# AD628.net
KiCad netlist of a schematic drawn in Altium Designer
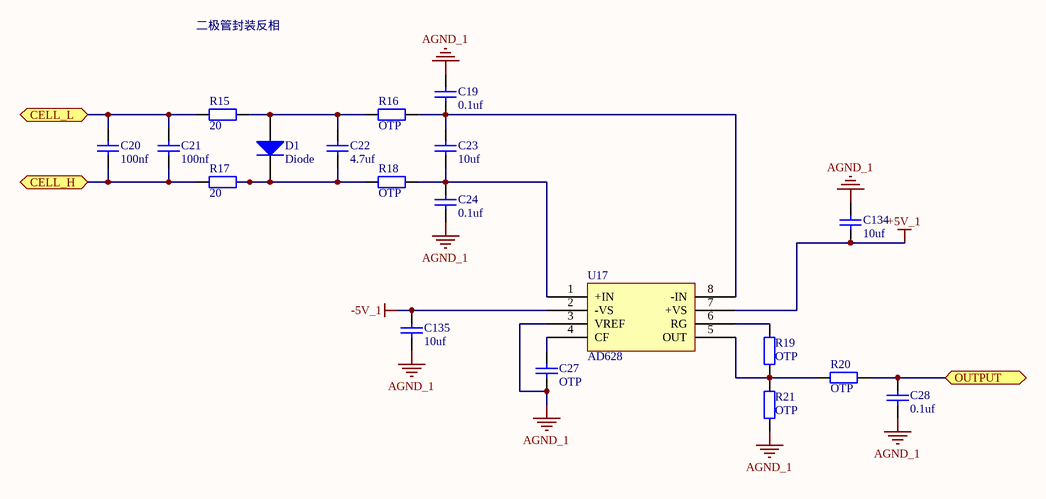
[diagram p0: AD628模块.SchDoc]

(export (version "E")
  (design (tool "Eeschema 10.0.6"))
  (components
    (comp (ref "C19")
      (value "0.1uf")
      (footprint "0805C")
      (description "Capacitor")
      (fields (field (name "Comment") "Cap") (field (name "PUBLISHER") "Altium Limited"))
      (libsource (lib "Miscellaneous Devices") (part "Cap"))
    )
    (comp (ref "C20")
      (value "100nf")
      (footprint "0805C")
      (description "Capacitor")
      (fields (field (name "Comment") "Cap") (field (name "PUBLISHER") "Altium Limited"))
      (libsource (lib "Miscellaneous Devices") (part "Cap"))
    )
    (comp (ref "C21")
      (value "100nf")
      (footprint "0805C")
      (description "Capacitor")
      (fields (field (name "Comment") "Cap") (field (name "PUBLISHER") "Altium Limited"))
      (libsource (lib "Miscellaneous Devices") (part "Cap"))
    )
    (comp (ref "C22")
      (value "4.7uf")
      (footprint "0805C")
      (description "Capacitor")
      (fields (field (name "Comment") "Cap") (field (name "PUBLISHER") "Altium Limited"))
      (libsource (lib "Miscellaneous Devices") (part "Cap"))
    )
    (comp (ref "C23")
      (value "10uf")
      (footprint "0805C")
      (description "Capacitor")
      (fields (field (name "Comment") "Cap") (field (name "PUBLISHER") "Altium Limited"))
      (libsource (lib "Miscellaneous Devices") (part "Cap"))
    )
    (comp (ref "C24")
      (value "0.1uf")
      (footprint "0805C")
      (description "Capacitor")
      (fields (field (name "Comment") "Cap") (field (name "PUBLISHER") "Altium Limited"))
      (libsource (lib "Miscellaneous Devices") (part "Cap"))
    )
    (comp (ref "C27")
      (value "OTP")
      (footprint "0805C")
      (description "Capacitor")
      (fields (field (name "Comment") "Cap") (field (name "PUBLISHER") "Altium Limited"))
      (libsource (lib "Miscellaneous Devices") (part "Cap"))
    )
    (comp (ref "C28")
      (value "0.1uf")
      (footprint "0805C")
      (description "Capacitor")
      (fields (field (name "Comment") "Cap") (field (name "PUBLISHER") "Altium Limited"))
      (libsource (lib "Miscellaneous Devices") (part "Cap"))
    )
    (comp (ref "C134")
      (value "10uf")
      (footprint "0805C")
      (description "Capacitor")
      (fields (field (name "Comment") "Cap") (field (name "PUBLISHER") "Altium Limited"))
      (libsource (lib "Miscellaneous Devices") (part "Cap"))
    )
    (comp (ref "C135")
      (value "10uf")
      (footprint "0805C")
      (description "Capacitor")
      (fields (field (name "Comment") "Cap") (field (name "PUBLISHER") "Altium Limited"))
      (libsource (lib "Miscellaneous Devices") (part "Cap"))
    )
    (comp (ref "D1")
      (value "Diode")
      (footprint "SMA")
      (description "Default Diode")
      (fields (field (name "PUBLISHER") "Altium Limited"))
      (libsource (lib "Miscellaneous Devices") (part "Diode"))
    )
    (comp (ref "R15")
      (value "20")
      (footprint "0805R")
      (description "Resistor")
      (fields (field (name "Comment") "Res2") (field (name "PUBLISHER") "Altium Limited"))
      (libsource (lib "Miscellaneous Devices") (part "Res2"))
    )
    (comp (ref "R16")
      (value "OTP")
      (footprint "0805R")
      (description "Resistor")
      (fields (field (name "Comment") "Res2") (field (name "PUBLISHER") "Altium Limited"))
      (libsource (lib "Miscellaneous Devices") (part "Res2"))
    )
    (comp (ref "R17")
      (value "20")
      (footprint "0805R")
      (description "Resistor")
      (fields (field (name "Comment") "Res2") (field (name "PUBLISHER") "Altium Limited"))
      (libsource (lib "Miscellaneous Devices") (part "Res2"))
    )
    (comp (ref "R18")
      (value "OTP")
      (footprint "0805R")
      (description "Resistor")
      (fields (field (name "Comment") "Res2") (field (name "PUBLISHER") "Altium Limited"))
      (libsource (lib "Miscellaneous Devices") (part "Res2"))
    )
    (comp (ref "R19")
      (value "OTP")
      (footprint "0805R")
      (description "Resistor")
      (fields (field (name "Comment") "Res2") (field (name "PUBLISHER") "Altium Limited"))
      (libsource (lib "") (part "Res2_1"))
    )
    (comp (ref "R20")
      (value "OTP")
      (footprint "0805R")
      (description "Resistor")
      (fields (field (name "Comment") "Res2") (field (name "PUBLISHER") "Altium Limited"))
      (libsource (lib "Miscellaneous Devices") (part "Res2"))
    )
    (comp (ref "R21")
      (value "OTP")
      (footprint "0805R")
      (description "Resistor")
      (fields (field (name "Comment") "Res2") (field (name "PUBLISHER") "Altium Limited"))
      (libsource (lib "") (part "Res2_1"))
    )
    (comp (ref "U17") (value "AD628") (footprint "MSOP8") (libsource (lib "ic_lib") (part "AD628")))
  )
  (nets
    (net (code "1") (name "+5V_1") (class "Default")
      (node (ref "C134") (pin "2") (pinfunction "2_2") (pintype "passive"))
      (node (ref "U17") (pin "7") (pinfunction "+VS_7") (pintype "passive"))
    )
    (net (code "2") (name "-5V_1") (class "Default")
      (node (ref "C135") (pin "2") (pinfunction "2_2") (pintype "passive"))
      (node (ref "U17") (pin "2") (pinfunction "-VS_2") (pintype "passive"))
    )
    (net (code "3") (name "/CELL_H") (class "Default")
      (node (ref "C20") (pin "1") (pinfunction "1_1") (pintype "passive"))
      (node (ref "C21") (pin "1") (pinfunction "1_1") (pintype "passive"))
      (node (ref "R17") (pin "2") (pinfunction "2_2") (pintype "passive"))
    )
    (net (code "4") (name "/CELL_L") (class "Default")
      (node (ref "C20") (pin "2") (pinfunction "2_2") (pintype "passive"))
      (node (ref "C21") (pin "2") (pinfunction "2_2") (pintype "passive"))
      (node (ref "R15") (pin "2") (pinfunction "2_2") (pintype "passive"))
    )
    (net (code "5") (name "/OUTPUT") (class "Default")
      (node (ref "C28") (pin "2") (pinfunction "2_2") (pintype "passive"))
      (node (ref "R20") (pin "1") (pinfunction "1_1") (pintype "passive"))
    )
    (net (code "6") (name "AGND_1") (class "Default")
      (node (ref "C134") (pin "1") (pinfunction "1_1") (pintype "passive"))
      (node (ref "C135") (pin "1") (pinfunction "1_1") (pintype "passive"))
      (node (ref "C19") (pin "2") (pinfunction "2_2") (pintype "passive"))
      (node (ref "C24") (pin "1") (pinfunction "1_1") (pintype "passive"))
      (node (ref "C27") (pin "1") (pinfunction "1_1") (pintype "passive"))
      (node (ref "C28") (pin "1") (pinfunction "1_1") (pintype "passive"))
      (node (ref "R21") (pin "1") (pinfunction "1_1") (pintype "passive"))
      (node (ref "U17") (pin "3") (pinfunction "VREF_3") (pintype "passive"))
    )
    (net (code "7") (name "Net-(D1-A)") (class "Default")
      (node (ref "C22") (pin "2") (pinfunction "2_2") (pintype "passive"))
      (node (ref "D1") (pin "1") (pinfunction "A_1") (pintype "passive"))
      (node (ref "R15") (pin "1") (pinfunction "1_1") (pintype "passive"))
      (node (ref "R16") (pin "2") (pinfunction "2_2") (pintype "passive"))
    )
    (net (code "8") (name "Net-(D1-K)") (class "Default")
      (node (ref "C22") (pin "1") (pinfunction "1_1") (pintype "passive"))
      (node (ref "D1") (pin "2") (pinfunction "K_2") (pintype "passive"))
      (node (ref "R17") (pin "1") (pinfunction "1_1") (pintype "passive"))
      (node (ref "R18") (pin "2") (pinfunction "2_2") (pintype "passive"))
    )
    (net (code "9") (name "Net-(U17-+IN)") (class "Default")
      (node (ref "C23") (pin "1") (pinfunction "1_1") (pintype "passive"))
      (node (ref "C24") (pin "2") (pinfunction "2_2") (pintype "passive"))
      (node (ref "R18") (pin "1") (pinfunction "1_1") (pintype "passive"))
      (node (ref "U17") (pin "1") (pinfunction "+IN_1") (pintype "passive"))
    )
    (net (code "10") (name "Net-(U17--IN)") (class "Default")
      (node (ref "C19") (pin "1") (pinfunction "1_1") (pintype "passive"))
      (node (ref "C23") (pin "2") (pinfunction "2_2") (pintype "passive"))
      (node (ref "R16") (pin "1") (pinfunction "1_1") (pintype "passive"))
      (node (ref "U17") (pin "8") (pinfunction "-IN_8") (pintype "passive"))
    )
    (net (code "11") (name "Net-(U17-CF)") (class "Default")
      (node (ref "C27") (pin "2") (pinfunction "2_2") (pintype "passive"))
      (node (ref "U17") (pin "4") (pinfunction "CF_4") (pintype "passive"))
    )
    (net (code "12") (name "Net-(U17-OUT)") (class "Default")
      (node (ref "R19") (pin "1") (pinfunction "1_1") (pintype "passive"))
      (node (ref "R20") (pin "2") (pinfunction "2_2") (pintype "passive"))
      (node (ref "R21") (pin "2") (pinfunction "2_2") (pintype "passive"))
      (node (ref "U17") (pin "5") (pinfunction "OUT_5") (pintype "passive"))
    )
    (net (code "13") (name "Net-(U17-RG)") (class "Default")
      (node (ref "R19") (pin "2") (pinfunction "2_2") (pintype "passive"))
      (node (ref "U17") (pin "6") (pinfunction "RG_6") (pintype "passive"))
    )
  )
)
